# SmartSwitch433SCH.net
KiCad netlist of a schematic drawn in Altium Designer
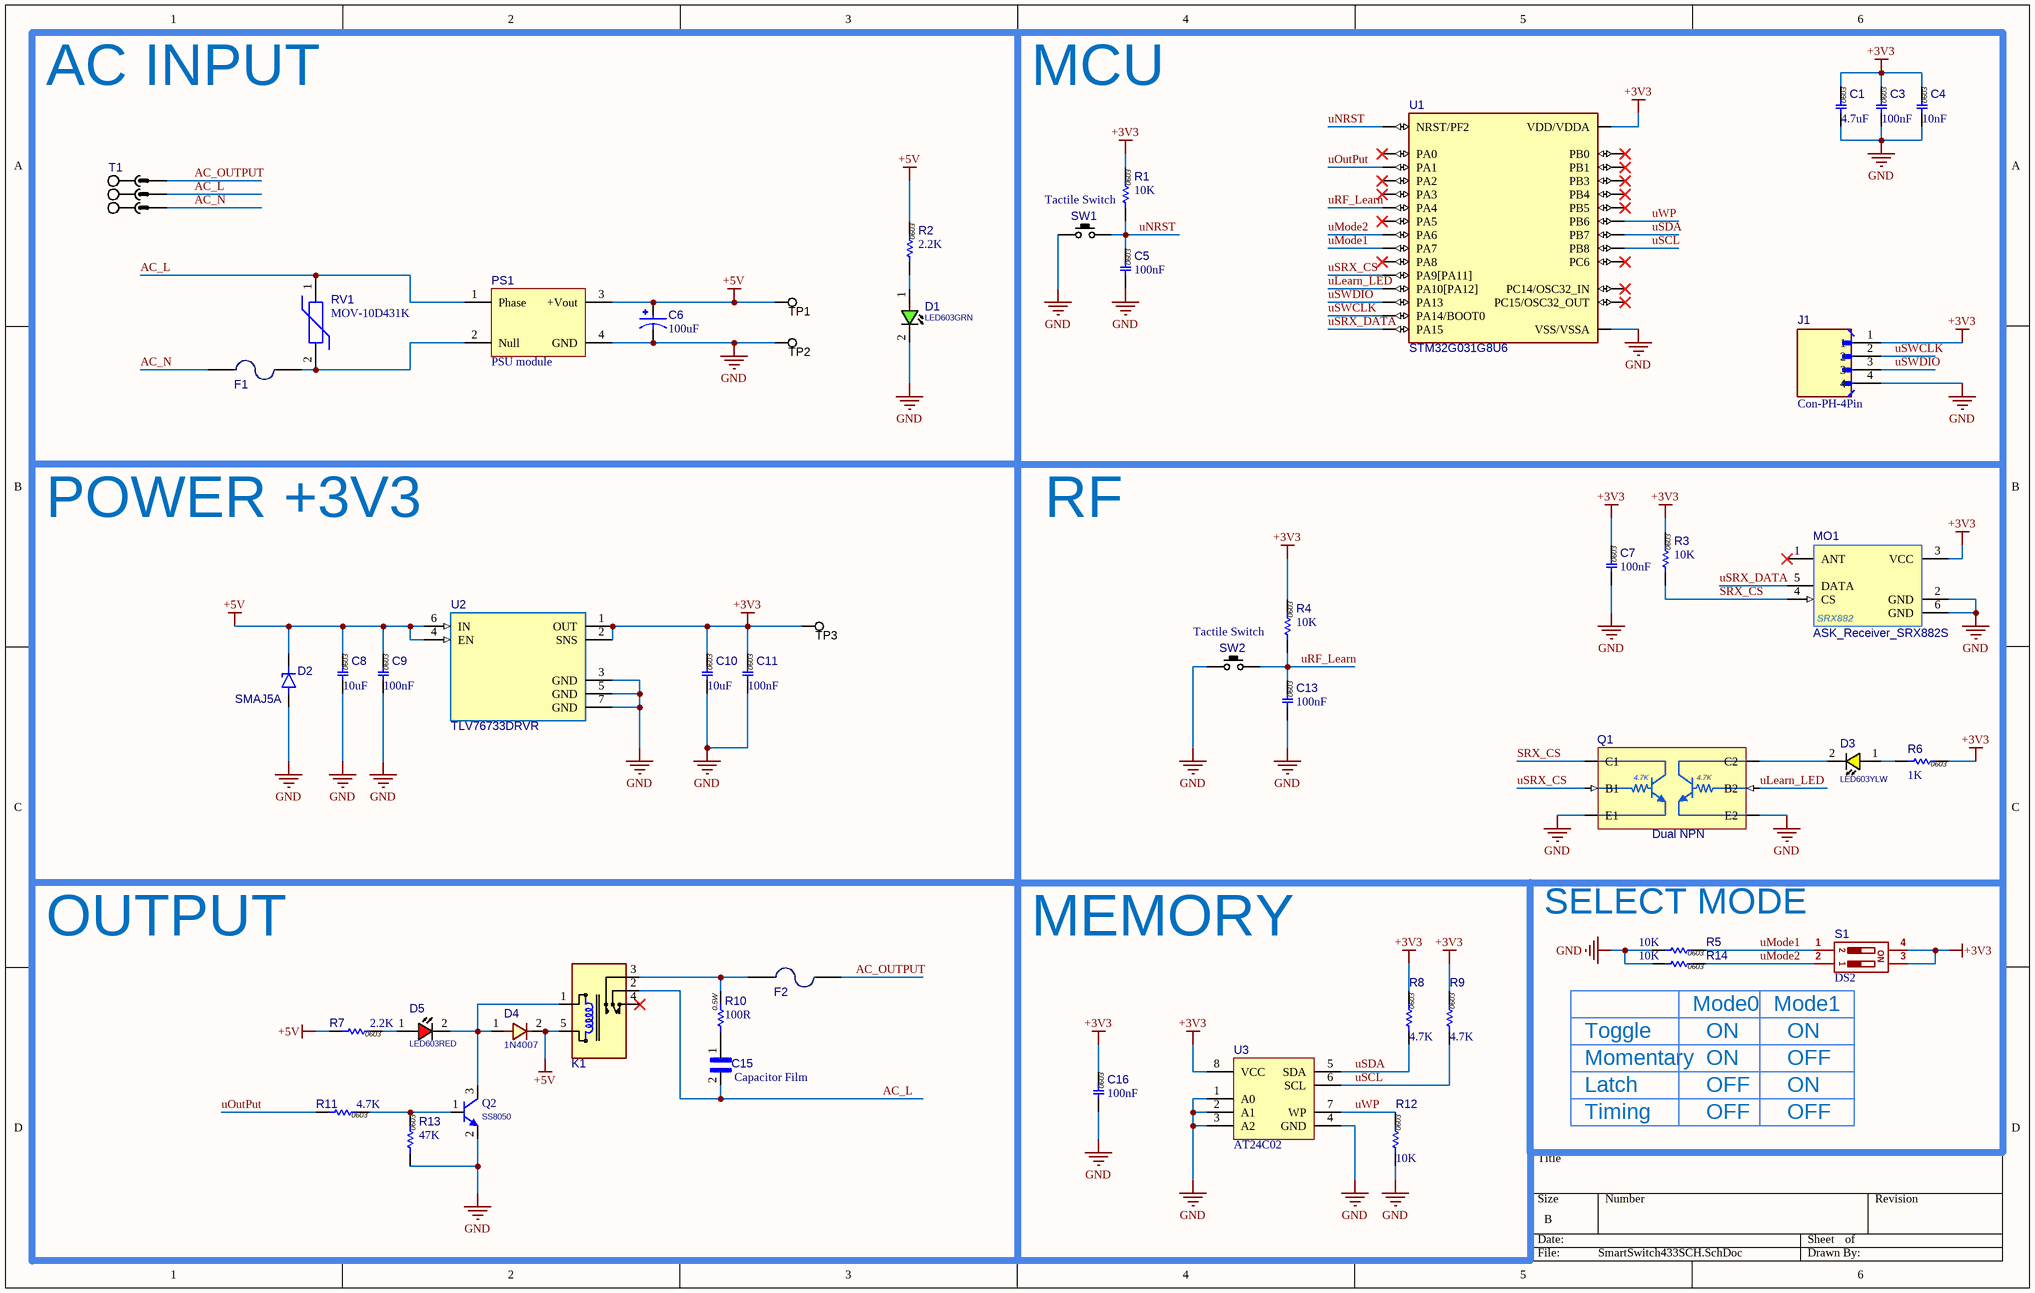
[diagram p0: SmartSwitch433SCH.SchDoc]

(export (version "E")
  (design (tool "Eeschema 10.0.6"))
  (components
    (comp (ref "C1")
      (value "4.7uF")
      (footprint "Cap SMD 0603")
      (libsource (lib "Mehrdad") (part "Cap SMD 0603"))
    )
    (comp (ref "C3")
      (value "100nF")
      (footprint "Cap SMD 0603")
      (libsource (lib "Mehrdad") (part "Cap SMD 0603"))
    )
    (comp (ref "C4")
      (value "10nF")
      (footprint "Cap SMD 0603")
      (libsource (lib "Mehrdad") (part "Cap SMD 0603"))
    )
    (comp (ref "C5")
      (value "100nF")
      (footprint "Cap SMD 0603")
      (libsource (lib "Mehrdad") (part "Cap SMD 0603"))
    )
    (comp (ref "C6")
      (value "100uF")
      (footprint "Cap Electrolytic Radial . 6.3 * 12")
      (libsource (lib "Mehrdad") (part "Cap Electrolytic Radial . 6.3 * 12"))
    )
    (comp (ref "C7")
      (value "100nF")
      (footprint "Cap SMD 0603")
      (libsource (lib "Mehrdad") (part "Cap SMD 0603"))
    )
    (comp (ref "C8")
      (value "10uF")
      (footprint "Cap SMD 0603")
      (libsource (lib "Mehrdad") (part "Cap SMD 0603"))
    )
    (comp (ref "C9")
      (value "100nF")
      (footprint "Cap SMD 0603")
      (libsource (lib "Mehrdad") (part "Cap SMD 0603"))
    )
    (comp (ref "C10")
      (value "10uF")
      (footprint "Cap SMD 0603")
      (libsource (lib "Mehrdad") (part "Cap SMD 0603"))
    )
    (comp (ref "C11")
      (value "100nF")
      (footprint "Cap SMD 0603")
      (libsource (lib "Mehrdad") (part "Cap SMD 0603"))
    )
    (comp (ref "C13")
      (value "100nF")
      (footprint "Cap SMD 0603")
      (libsource (lib "Mehrdad") (part "Cap SMD 0603"))
    )
    (comp (ref "C15")
      (value "Capacitor Film")
      (footprint "Capacitor Film2")
      (description "Capacitor Film Pitch=10mm")
      (libsource (lib "Mehrdad") (part "Capacitor Film"))
    )
    (comp (ref "C16")
      (value "100nF")
      (footprint "Cap SMD 0603")
      (libsource (lib "Mehrdad") (part "Cap SMD 0603"))
    )
    (comp (ref "D1")
      (value "LED603GRN")
      (footprint "LED0603GRN")
      (description "LED, SMD, 0603, GREEN")
      (fields (field (name "MANF") "Kingbright") (field (name "MANF_P#") "APT1608SGC"))
      (libsource (lib "led(diode)") (part "LED_SMD_0603_GRN"))
    )
    (comp (ref "D2")
      (value "SMAJ5A")
      (footprint "SMAJ15A")
      (description "TVS Diode Uni-directional 15V SMA  BR Voltage : 16.7V  Clamping Volatage : 24.4V")
      (libsource (lib "Mehrdad") (part "SMAJ15A"))
    )
    (comp (ref "D3")
      (value "LED603YLW")
      (footprint "LED0603YLW")
      (description "LED, SMD, 0603, YELLOW")
      (fields (field (name "MANF") "MANF") (field (name "MANF_P#") "MANF_PART#"))
      (libsource (lib "led(diode)") (part "LED_SMD_0603_YLW"))
    )
    (comp (ref "D4")
      (value "1N4007")
      (footprint "D_SMA")
      (description "DIODE, GENERAL PURPOSE, 1000V/1A")
      (fields (field (name "MANF") "Kingtronics") (field (name "MANF_P#") "M7"))
      (libsource (lib "diode") (part "DIODE_SMD_1N4007"))
    )
    (comp (ref "D5")
      (value "LED603RED")
      (footprint "LED0603RED")
      (description "LED, SMD, 0603, RED")
      (fields (field (name "MANF") "MANF") (field (name "MANF_P#") "MANF_PART#"))
      (libsource (lib "led(diode)") (part "LED_SMD_0603_RED"))
    )
    (comp (ref "F1")
      (value "250V-0.2A")
      (footprint "Fuse 5x20")
      (description "Fuses 5x20")
      (fields (field (name "PUBLISHER") "Majid Derhambakhsh"))
      (libsource (lib "mBedLab Altium Library (2024-04-20)") (part "Fuse 5x20-Holder"))
    )
    (comp (ref "F2")
      (value "250V-0.2A")
      (footprint "Fuse 5x20")
      (description "Fuses 5x20")
      (fields (field (name "PUBLISHER") "Majid Derhambakhsh"))
      (libsource (lib "mBedLab Altium Library (2024-04-20)") (part "Fuse 5x20-Holder"))
    )
    (comp (ref "J1")
      (value "Con-PH-4Pin")
      (footprint "Con-PH-4Pin-ST")
      (description "Connector Header Through Hole 4 position 0.079 (2.00mm)")
      (libsource (lib "Mehrdad") (part "Con-PH-4Pin"))
    )
    (comp (ref "K1")
      (value "Relay")
      (footprint "Relay-G5Q-14")
      (description "General Purpose Sealed Relay SPDT")
      (libsource (lib "Mehrdad") (part "Relay"))
    )
    (comp (ref "MO1")
      (value "ASK_Receiver_SRX882S")
      (footprint "ASK_Receiver_SRX882S")
      (description "RF Receiver 315/433Mhz")
      (libsource (lib "Mehrdad") (part "ASK_Receiver_SRX882S"))
    )
    (comp (ref "PS1")
      (value "PSU module")
      (footprint "PSU module 3W")
      (description "AC / DC Converter")
      (libsource (lib "Mehrdad") (part "PSU module"))
    )
    (comp (ref "Q1")
      (value "Dual NPN")
      (footprint "PUMH7")
      (description "2 NPN 50V 100mA Transistors (Resistor-Equipped R1 = 4.7kΩ) SOT-363")
      (libsource (lib "Mehrdad") (part "PUMH7"))
    )
    (comp (ref "Q2")
      (value "SS8050")
      (footprint "SOT23_3")
      (description "BJT, NPN, 25v, 1.5A, SMD, SOT23")
      (fields (field (name "MANF") "GALAXY"))
      (libsource (lib "transistor_bjt") (part "NPN_SS8050_SOT23"))
    )
    (comp (ref "R1")
      (value "10K")
      (footprint "Res SMD 0603")
      (libsource (lib "Mehrdad") (part "Res SMD 0603"))
    )
    (comp (ref "R2")
      (value "2.2K")
      (footprint "Res SMD 0603")
      (libsource (lib "Mehrdad") (part "Res SMD 0603"))
    )
    (comp (ref "R3")
      (value "10K")
      (footprint "Res SMD 0603")
      (libsource (lib "Mehrdad") (part "Res SMD 0603"))
    )
    (comp (ref "R4")
      (value "10K")
      (footprint "Res SMD 0603")
      (libsource (lib "Mehrdad") (part "Res SMD 0603"))
    )
    (comp (ref "R5")
      (value "10K")
      (footprint "Res SMD 0603")
      (libsource (lib "Mehrdad") (part "Res SMD 0603"))
    )
    (comp (ref "R6")
      (value "1K")
      (footprint "Res SMD 0603")
      (libsource (lib "Mehrdad") (part "Res SMD 0603"))
    )
    (comp (ref "R7")
      (value "2.2K")
      (footprint "Res SMD 0603")
      (libsource (lib "Mehrdad") (part "Res SMD 0603"))
    )
    (comp (ref "R8")
      (value "4.7K")
      (footprint "Res SMD 0603")
      (libsource (lib "Mehrdad") (part "Res SMD 0603"))
    )
    (comp (ref "R9")
      (value "4.7K")
      (footprint "Res SMD 0603")
      (libsource (lib "Mehrdad") (part "Res SMD 0603"))
    )
    (comp (ref "R10")
      (value "100R")
      (footprint "Res THD 0.5w")
      (description "Resistor 1/2W")
      (libsource (lib "Mehrdad") (part "Res THD 0.5w"))
    )
    (comp (ref "R11")
      (value "4.7K")
      (footprint "Res SMD 0603")
      (libsource (lib "Mehrdad") (part "Res SMD 0603"))
    )
    (comp (ref "R12")
      (value "10K")
      (footprint "Res SMD 0603")
      (libsource (lib "Mehrdad") (part "Res SMD 0603"))
    )
    (comp (ref "R13")
      (value "47K")
      (footprint "Res SMD 0603")
      (libsource (lib "Mehrdad") (part "Res SMD 0603"))
    )
    (comp (ref "R14")
      (value "10K")
      (footprint "Res SMD 0603")
      (libsource (lib "Mehrdad") (part "Res SMD 0603"))
    )
    (comp (ref "RV1")
      (value "MOV-10D431K")
      (footprint "MOV-10D391K")
      (libsource (lib "Mehrdad") (part "MOV-10D391K"))
    )
    (comp (ref "S1")
      (value "DS2")
      (footprint "DIP Switch x2")
      (description "2 BIT DIP Switch")
      (fields (field (name "PUBLISHER") "Majid Derhambakhsh"))
      (libsource (lib "mBedLab Altium Library (2024-04-20)") (part "DIP Switch 2"))
    )
    (comp (ref "SW1")
      (value "Tactile Switch")
      (footprint "Tactil Switch 3*4*2")
      (description "3x6x5 mm - 2 Pin")
      (libsource (lib "Mehrdad") (part "Tactile Switch"))
    )
    (comp (ref "SW2")
      (value "Tactile Switch")
      (footprint "Tactile Switch 3*6*5")
      (libsource (lib "Mehrdad") (part "Tactile Switch"))
    )
    (comp (ref "T1")
      (value "~")
      (footprint "MSTB 2,5/3-G-5,08")
      (description "3 Pitch: 5.08 mm Color: green Contact surface: Tin Assembly")
      (fields
        (field (name "VOLTAGE") "320 V")
        (field (name "MP") "PHOENIX")
        (field (name "PUBLISHER") "Majid Derhambakhsh")
      )
      (libsource (lib "mBedLab Altium Library (2024-04-20)") (part "Phoenix MSTB-03"))
    )
    (comp (ref "TP1")
      (value "TESTPOINT_SMD")
      (footprint "TPSMD_S1")
      (description "TEST POINT")
      (fields (field (name "MANF") "MANF") (field (name "MANF_P#") "MANF_P#"))
      (libsource (lib "test-tp_jumper") (part "TESTPOINT_SMD"))
    )
    (comp (ref "TP2")
      (value "TESTPOINT_SMD")
      (footprint "TPSMD_S1")
      (description "TEST POINT")
      (fields (field (name "MANF") "MANF") (field (name "MANF_P#") "MANF_P#"))
      (libsource (lib "test-tp_jumper") (part "TESTPOINT_SMD"))
    )
    (comp (ref "TP3")
      (value "TESTPOINT_SMD")
      (footprint "TPSMD_S1")
      (description "TEST POINT")
      (fields (field (name "MANF") "MANF") (field (name "MANF_P#") "MANF_P#"))
      (libsource (lib "test-tp_jumper") (part "TESTPOINT_SMD"))
    )
    (comp (ref "U1")
      (value "STM32G031G8U6")
      (footprint "STM32G031G8U6")
      (description "ARM Cortex-M0+ STM32G0 Microcontroller IC 32-Bit 64MHz 64KB (64K x 8) FLASH 28-UFQFPN (4x4)")
      (libsource (lib "Mehrdad") (part "STM32G031G8U6"))
    )
    (comp (ref "U2")
      (value "TLV76733DRVR")
      (footprint "TLV76733DRVR")
      (description "Adjustable- and fixed-output, 1-A, 16-V, positive-voltage low-dropout (LDO) linear regulator")
      (libsource (lib "Mehrdad") (part "TLV76733DRVR"))
    )
    (comp (ref "U3")
      (value "AT24C02")
      (footprint "SO8_NARROW_N")
      (description "EEPROM Memory")
      (fields (field (name "VALIDATION") "Valid"))
      (libsource (lib "aKaReZa") (part "IC_Memory_AT24C02"))
    )
  )
  (nets
    (net (code "1") (name "+3V3") (class "Default")
      (node (ref "C1") (pin "2") (pinfunction "2_2") (pintype "passive"))
      (node (ref "C10") (pin "2") (pinfunction "2_2") (pintype "passive"))
      (node (ref "C11") (pin "2") (pinfunction "2_2") (pintype "passive"))
      (node (ref "C16") (pin "2") (pinfunction "2_2") (pintype "passive"))
      (node (ref "C3") (pin "2") (pinfunction "2_2") (pintype "passive"))
      (node (ref "C4") (pin "2") (pinfunction "2_2") (pintype "passive"))
      (node (ref "C7") (pin "2") (pinfunction "2_2") (pintype "passive"))
      (node (ref "J1") (pin "1") (pinfunction "1_1") (pintype "passive"))
      (node (ref "MO1") (pin "3") (pinfunction "VCC_3") (pintype "power_in"))
      (node (ref "R1") (pin "2") (pinfunction "2_2") (pintype "passive"))
      (node (ref "R3") (pin "2") (pinfunction "2_2") (pintype "passive"))
      (node (ref "R4") (pin "2") (pinfunction "2_2") (pintype "passive"))
      (node (ref "R6") (pin "2") (pinfunction "2_2") (pintype "passive"))
      (node (ref "R8") (pin "2") (pinfunction "2_2") (pintype "passive"))
      (node (ref "R9") (pin "2") (pinfunction "2_2") (pintype "passive"))
      (node (ref "S1") (pin "3") (pinfunction "3_3") (pintype "passive"))
      (node (ref "S1") (pin "4") (pinfunction "4_4") (pintype "passive"))
      (node (ref "TP3") (pin "1") (pinfunction "1_1") (pintype "passive"))
      (node (ref "U1") (pin "3") (pinfunction "VDD/VDDA_3") (pintype "power_in"))
      (node (ref "U2") (pin "1") (pinfunction "OUT_1") (pintype "passive"))
      (node (ref "U2") (pin "2") (pinfunction "SNS_2") (pintype "passive"))
      (node (ref "U3") (pin "8") (pinfunction "VCC_8") (pintype "passive"))
    )
    (net (code "2") (name "+5V") (class "Default")
      (node (ref "C6") (pin "P") (pinfunction "P_P") (pintype "passive"))
      (node (ref "C8") (pin "2") (pinfunction "2_2") (pintype "passive"))
      (node (ref "C9") (pin "2") (pinfunction "2_2") (pintype "passive"))
      (node (ref "D2") (pin "C") (pinfunction "C_C") (pintype "passive"))
      (node (ref "D4") (pin "2") (pinfunction "2_2") (pintype "passive"))
      (node (ref "K1") (pin "5") (pinfunction "T2_5") (pintype "passive"))
      (node (ref "PS1") (pin "3") (pinfunction "+Vout_3") (pintype "power_in"))
      (node (ref "R2") (pin "2") (pinfunction "2_2") (pintype "passive"))
      (node (ref "R7") (pin "1") (pinfunction "1_1") (pintype "passive"))
      (node (ref "TP1") (pin "1") (pinfunction "1_1") (pintype "passive"))
      (node (ref "U2") (pin "4") (pinfunction "EN_4") (pintype "input"))
      (node (ref "U2") (pin "6") (pinfunction "IN_6") (pintype "input"))
    )
    (net (code "3") (name "/AC_L") (class "Default")
      (node (ref "C15") (pin "2") (pinfunction "2_2") (pintype "passive"))
      (node (ref "K1") (pin "2") (pinfunction "COM_2") (pintype "passive"))
      (node (ref "PS1") (pin "1") (pinfunction "Phase_1") (pintype "power_in"))
      (node (ref "RV1") (pin "1") (pinfunction "1_1") (pintype "power_in"))
      (node (ref "T1") (pin "2") (pinfunction "2_2") (pintype "passive"))
    )
    (net (code "4") (name "/AC_N") (class "Default")
      (node (ref "F1") (pin "1") (pinfunction "1_1") (pintype "passive"))
      (node (ref "T1") (pin "3") (pinfunction "3_3") (pintype "passive"))
    )
    (net (code "5") (name "/AC_OUTPUT") (class "Default")
      (node (ref "F2") (pin "2") (pinfunction "2_2") (pintype "passive"))
      (node (ref "T1") (pin "1") (pinfunction "1_1") (pintype "passive"))
    )
    (net (code "6") (name "/SRX_CS") (class "Default")
      (node (ref "MO1") (pin "4") (pinfunction "CS_4") (pintype "input"))
      (node (ref "Q1") (pin "6") (pinfunction "C1_6") (pintype "power_in"))
      (node (ref "R3") (pin "1") (pinfunction "1_1") (pintype "passive"))
    )
    (net (code "7") (name "/uLearn_LED") (class "Default")
      (node (ref "Q1") (pin "5") (pinfunction "B2_5") (pintype "input"))
      (node (ref "U1") (pin "19") (pinfunction "PA10[PA12]_19") (pintype "bidirectional"))
    )
    (net (code "8") (name "/uMode1") (class "Default")
      (node (ref "R5") (pin "2") (pinfunction "2_2") (pintype "passive"))
      (node (ref "S1") (pin "1") (pinfunction "1_1") (pintype "passive"))
      (node (ref "U1") (pin "13") (pinfunction "PA7_13") (pintype "bidirectional"))
    )
    (net (code "9") (name "/uMode2") (class "Default")
      (node (ref "R14") (pin "2") (pinfunction "2_2") (pintype "passive"))
      (node (ref "S1") (pin "2") (pinfunction "2_2") (pintype "passive"))
      (node (ref "U1") (pin "12") (pinfunction "PA6_12") (pintype "bidirectional"))
    )
    (net (code "10") (name "/uNRST") (class "Default")
      (node (ref "C5") (pin "2") (pinfunction "2_2") (pintype "passive"))
      (node (ref "R1") (pin "1") (pinfunction "1_1") (pintype "passive"))
      (node (ref "SW1") (pin "2") (pinfunction "P3_2") (pintype "passive"))
      (node (ref "U1") (pin "5") (pinfunction "NRST/PF2_5") (pintype "bidirectional"))
    )
    (net (code "11") (name "/uOutPut") (class "Default")
      (node (ref "R11") (pin "1") (pinfunction "1_1") (pintype "passive"))
      (node (ref "U1") (pin "7") (pinfunction "PA1_7") (pintype "bidirectional"))
    )
    (net (code "12") (name "/uRF_Learn") (class "Default")
      (node (ref "C13") (pin "2") (pinfunction "2_2") (pintype "passive"))
      (node (ref "R4") (pin "1") (pinfunction "1_1") (pintype "passive"))
      (node (ref "SW2") (pin "2") (pinfunction "P3_2") (pintype "passive"))
      (node (ref "U1") (pin "10") (pinfunction "PA4_10") (pintype "bidirectional"))
    )
    (net (code "13") (name "/uSCL") (class "Default")
      (node (ref "R9") (pin "1") (pinfunction "1_1") (pintype "passive"))
      (node (ref "U1") (pin "28") (pinfunction "PB8_28") (pintype "bidirectional"))
      (node (ref "U3") (pin "6") (pinfunction "SCL_6") (pintype "passive"))
    )
    (net (code "14") (name "/uSDA") (class "Default")
      (node (ref "R8") (pin "1") (pinfunction "1_1") (pintype "passive"))
      (node (ref "U1") (pin "27") (pinfunction "PB7_27") (pintype "bidirectional"))
      (node (ref "U3") (pin "5") (pinfunction "SDA_5") (pintype "passive"))
    )
    (net (code "15") (name "/uSRX_CS") (class "Default")
      (node (ref "Q1") (pin "2") (pinfunction "B1_2") (pintype "input"))
      (node (ref "U1") (pin "18") (pinfunction "PA9[PA11]_18") (pintype "bidirectional"))
    )
    (net (code "16") (name "/uSRX_DATA") (class "Default")
      (node (ref "MO1") (pin "5") (pinfunction "DATA_5") (pintype "passive"))
      (node (ref "U1") (pin "22") (pinfunction "PA15_22") (pintype "bidirectional"))
    )
    (net (code "17") (name "/uSWCLK") (class "Default")
      (node (ref "J1") (pin "2") (pinfunction "2_2") (pintype "passive"))
      (node (ref "U1") (pin "21") (pinfunction "PA14/BOOT0_21") (pintype "bidirectional"))
    )
    (net (code "18") (name "/uSWDIO") (class "Default")
      (node (ref "J1") (pin "3") (pinfunction "3_3") (pintype "passive"))
      (node (ref "U1") (pin "20") (pinfunction "PA13_20") (pintype "bidirectional"))
    )
    (net (code "19") (name "/uWP") (class "Default")
      (node (ref "R12") (pin "2") (pinfunction "2_2") (pintype "passive"))
      (node (ref "U1") (pin "26") (pinfunction "PB6_26") (pintype "bidirectional"))
      (node (ref "U3") (pin "7") (pinfunction "WP_7") (pintype "passive"))
    )
    (net (code "20") (name "GND") (class "Default")
      (node (ref "C1") (pin "1") (pinfunction "1_1") (pintype "passive"))
      (node (ref "C10") (pin "1") (pinfunction "1_1") (pintype "passive"))
      (node (ref "C11") (pin "1") (pinfunction "1_1") (pintype "passive"))
      (node (ref "C13") (pin "1") (pinfunction "1_1") (pintype "passive"))
      (node (ref "C16") (pin "1") (pinfunction "1_1") (pintype "passive"))
      (node (ref "C3") (pin "1") (pinfunction "1_1") (pintype "passive"))
      (node (ref "C4") (pin "1") (pinfunction "1_1") (pintype "passive"))
      (node (ref "C5") (pin "1") (pinfunction "1_1") (pintype "passive"))
      (node (ref "C6") (pin "N") (pinfunction "N_N") (pintype "passive"))
      (node (ref "C7") (pin "1") (pinfunction "1_1") (pintype "passive"))
      (node (ref "C8") (pin "1") (pinfunction "1_1") (pintype "passive"))
      (node (ref "C9") (pin "1") (pinfunction "1_1") (pintype "passive"))
      (node (ref "D1") (pin "2") (pinfunction "CATHODE_2") (pintype "passive"))
      (node (ref "D2") (pin "A") (pinfunction "A_A") (pintype "passive"))
      (node (ref "J1") (pin "4") (pinfunction "4_4") (pintype "passive"))
      (node (ref "MO1") (pin "2") (pinfunction "GND_2") (pintype "power_in"))
      (node (ref "MO1") (pin "6") (pinfunction "GND_6") (pintype "power_in"))
      (node (ref "PS1") (pin "4") (pinfunction "GND_4") (pintype "power_in"))
      (node (ref "Q1") (pin "1") (pinfunction "E1_1") (pintype "power_in"))
      (node (ref "Q1") (pin "4") (pinfunction "E2_4") (pintype "power_in"))
      (node (ref "Q2") (pin "2") (pinfunction "E_2") (pintype "passive"))
      (node (ref "R12") (pin "1") (pinfunction "1_1") (pintype "passive"))
      (node (ref "R13") (pin "1") (pinfunction "1_1") (pintype "passive"))
      (node (ref "R14") (pin "1") (pinfunction "1_1") (pintype "passive"))
      (node (ref "R5") (pin "1") (pinfunction "1_1") (pintype "passive"))
      (node (ref "SW1") (pin "1") (pinfunction "P1_1") (pintype "passive"))
      (node (ref "SW2") (pin "1") (pinfunction "P1_1") (pintype "passive"))
      (node (ref "TP2") (pin "1") (pinfunction "1_1") (pintype "passive"))
      (node (ref "U1") (pin "4") (pinfunction "VSS/VSSA_4") (pintype "power_in"))
      (node (ref "U2") (pin "3") (pinfunction "GND_3") (pintype "power_in"))
      (node (ref "U2") (pin "5") (pinfunction "GND_5") (pintype "power_in"))
      (node (ref "U2") (pin "7") (pinfunction "GND_7") (pintype "power_in"))
      (node (ref "U3") (pin "1") (pinfunction "A0_1") (pintype "passive"))
      (node (ref "U3") (pin "2") (pinfunction "A1_2") (pintype "passive"))
      (node (ref "U3") (pin "3") (pinfunction "A2_3") (pintype "passive"))
      (node (ref "U3") (pin "4") (pinfunction "GND_4") (pintype "passive"))
    )
    (net (code "21") (name "Net-(C15-Pad1)") (class "Default")
      (node (ref "C15") (pin "1") (pinfunction "1_1") (pintype "passive"))
      (node (ref "R10") (pin "1") (pinfunction "1_1") (pintype "passive"))
    )
    (net (code "22") (name "Net-(D1-ANODE)") (class "Default")
      (node (ref "D1") (pin "1") (pinfunction "ANODE_1") (pintype "passive"))
      (node (ref "R2") (pin "1") (pinfunction "1_1") (pintype "passive"))
    )
    (net (code "23") (name "Net-(D3-ANODE)") (class "Default")
      (node (ref "D3") (pin "1") (pinfunction "ANODE_1") (pintype "passive"))
      (node (ref "R6") (pin "1") (pinfunction "1_1") (pintype "passive"))
    )
    (net (code "24") (name "Net-(D3-CATHODE)") (class "Default")
      (node (ref "D3") (pin "2") (pinfunction "CATHODE_2") (pintype "passive"))
      (node (ref "Q1") (pin "3") (pinfunction "C2_3") (pintype "power_in"))
    )
    (net (code "25") (name "Net-(D5-ANODE)") (class "Default")
      (node (ref "D5") (pin "1") (pinfunction "ANODE_1") (pintype "passive"))
      (node (ref "R7") (pin "2") (pinfunction "2_2") (pintype "passive"))
    )
    (net (code "26") (name "Net-(D5-CATHODE)") (class "Default")
      (node (ref "D4") (pin "1") (pinfunction "1_1") (pintype "passive"))
      (node (ref "D5") (pin "2") (pinfunction "CATHODE_2") (pintype "passive"))
      (node (ref "K1") (pin "1") (pinfunction "T1_1") (pintype "passive"))
      (node (ref "Q2") (pin "3") (pinfunction "C_3") (pintype "passive"))
    )
    (net (code "27") (name "Net-(K1-NO)") (class "Default")
      (node (ref "F2") (pin "1") (pinfunction "1_1") (pintype "passive"))
      (node (ref "K1") (pin "3") (pinfunction "NO_3") (pintype "passive"))
      (node (ref "R10") (pin "2") (pinfunction "2_2") (pintype "passive"))
    )
    (net (code "28") (name "Net-(PS1-Null)") (class "Default")
      (node (ref "F1") (pin "2") (pinfunction "2_2") (pintype "passive"))
      (node (ref "PS1") (pin "2") (pinfunction "Null_2") (pintype "power_in"))
      (node (ref "RV1") (pin "2") (pinfunction "2_2") (pintype "power_in"))
    )
    (net (code "29") (name "Net-(Q2-B)") (class "Default")
      (node (ref "Q2") (pin "1") (pinfunction "B_1") (pintype "passive"))
      (node (ref "R11") (pin "2") (pinfunction "2_2") (pintype "passive"))
      (node (ref "R13") (pin "2") (pinfunction "2_2") (pintype "passive"))
    )
    (net (code "30") (name "unconnected-(K1-NC-Pad4)") (class "Default")
      (node (ref "K1") (pin "4") (pinfunction "NC_4") (pintype "passive+no_connect"))
    )
    (net (code "31") (name "unconnected-(MO1-ANT-Pad1)") (class "Default")
      (node (ref "MO1") (pin "1") (pinfunction "ANT_1") (pintype "passive+no_connect"))
    )
    (net (code "32") (name "unconnected-(U1-PA0-Pad6)") (class "Default")
      (node (ref "U1") (pin "6") (pinfunction "PA0_6") (pintype "bidirectional+no_connect"))
    )
    (net (code "33") (name "unconnected-(U1-PA2-Pad8)") (class "Default")
      (node (ref "U1") (pin "8") (pinfunction "PA2_8") (pintype "bidirectional+no_connect"))
    )
    (net (code "34") (name "unconnected-(U1-PA3-Pad9)") (class "Default")
      (node (ref "U1") (pin "9") (pinfunction "PA3_9") (pintype "bidirectional+no_connect"))
    )
    (net (code "35") (name "unconnected-(U1-PA5-Pad11)") (class "Default")
      (node (ref "U1") (pin "11") (pinfunction "PA5_11") (pintype "bidirectional+no_connect"))
    )
    (net (code "36") (name "unconnected-(U1-PA8-Pad16)") (class "Default")
      (node (ref "U1") (pin "16") (pinfunction "PA8_16") (pintype "bidirectional+no_connect"))
    )
    (net (code "37") (name "unconnected-(U1-PB0-Pad14)") (class "Default")
      (node (ref "U1") (pin "14") (pinfunction "PB0_14") (pintype "bidirectional+no_connect"))
    )
    (net (code "38") (name "unconnected-(U1-PB1-Pad15)") (class "Default")
      (node (ref "U1") (pin "15") (pinfunction "PB1_15") (pintype "bidirectional+no_connect"))
    )
    (net (code "39") (name "unconnected-(U1-PB3-Pad23)") (class "Default")
      (node (ref "U1") (pin "23") (pinfunction "PB3_23") (pintype "bidirectional+no_connect"))
    )
    (net (code "40") (name "unconnected-(U1-PB4-Pad24)") (class "Default")
      (node (ref "U1") (pin "24") (pinfunction "PB4_24") (pintype "bidirectional+no_connect"))
    )
    (net (code "41") (name "unconnected-(U1-PB5-Pad25)") (class "Default")
      (node (ref "U1") (pin "25") (pinfunction "PB5_25") (pintype "bidirectional+no_connect"))
    )
    (net (code "42") (name "unconnected-(U1-PC6-Pad17)") (class "Default")
      (node (ref "U1") (pin "17") (pinfunction "PC6_17") (pintype "bidirectional+no_connect"))
    )
    (net (code "43") (name "unconnected-(U1-PC14{slash}OSC32_IN-Pad1)") (class "Default")
      (node (ref "U1") (pin "1") (pinfunction "PC14/OSC32_IN_1") (pintype "bidirectional+no_connect"))
    )
    (net (code "44") (name "unconnected-(U1-PC15{slash}OSC32_OUT-Pad2)") (class "Default")
      (node (ref "U1") (pin "2") (pinfunction "PC15/OSC32_OUT_2") (pintype "bidirectional+no_connect"))
    )
  )
)
